# radio_hub_module.net
KiCad netlist of a schematic drawn in EAGLE
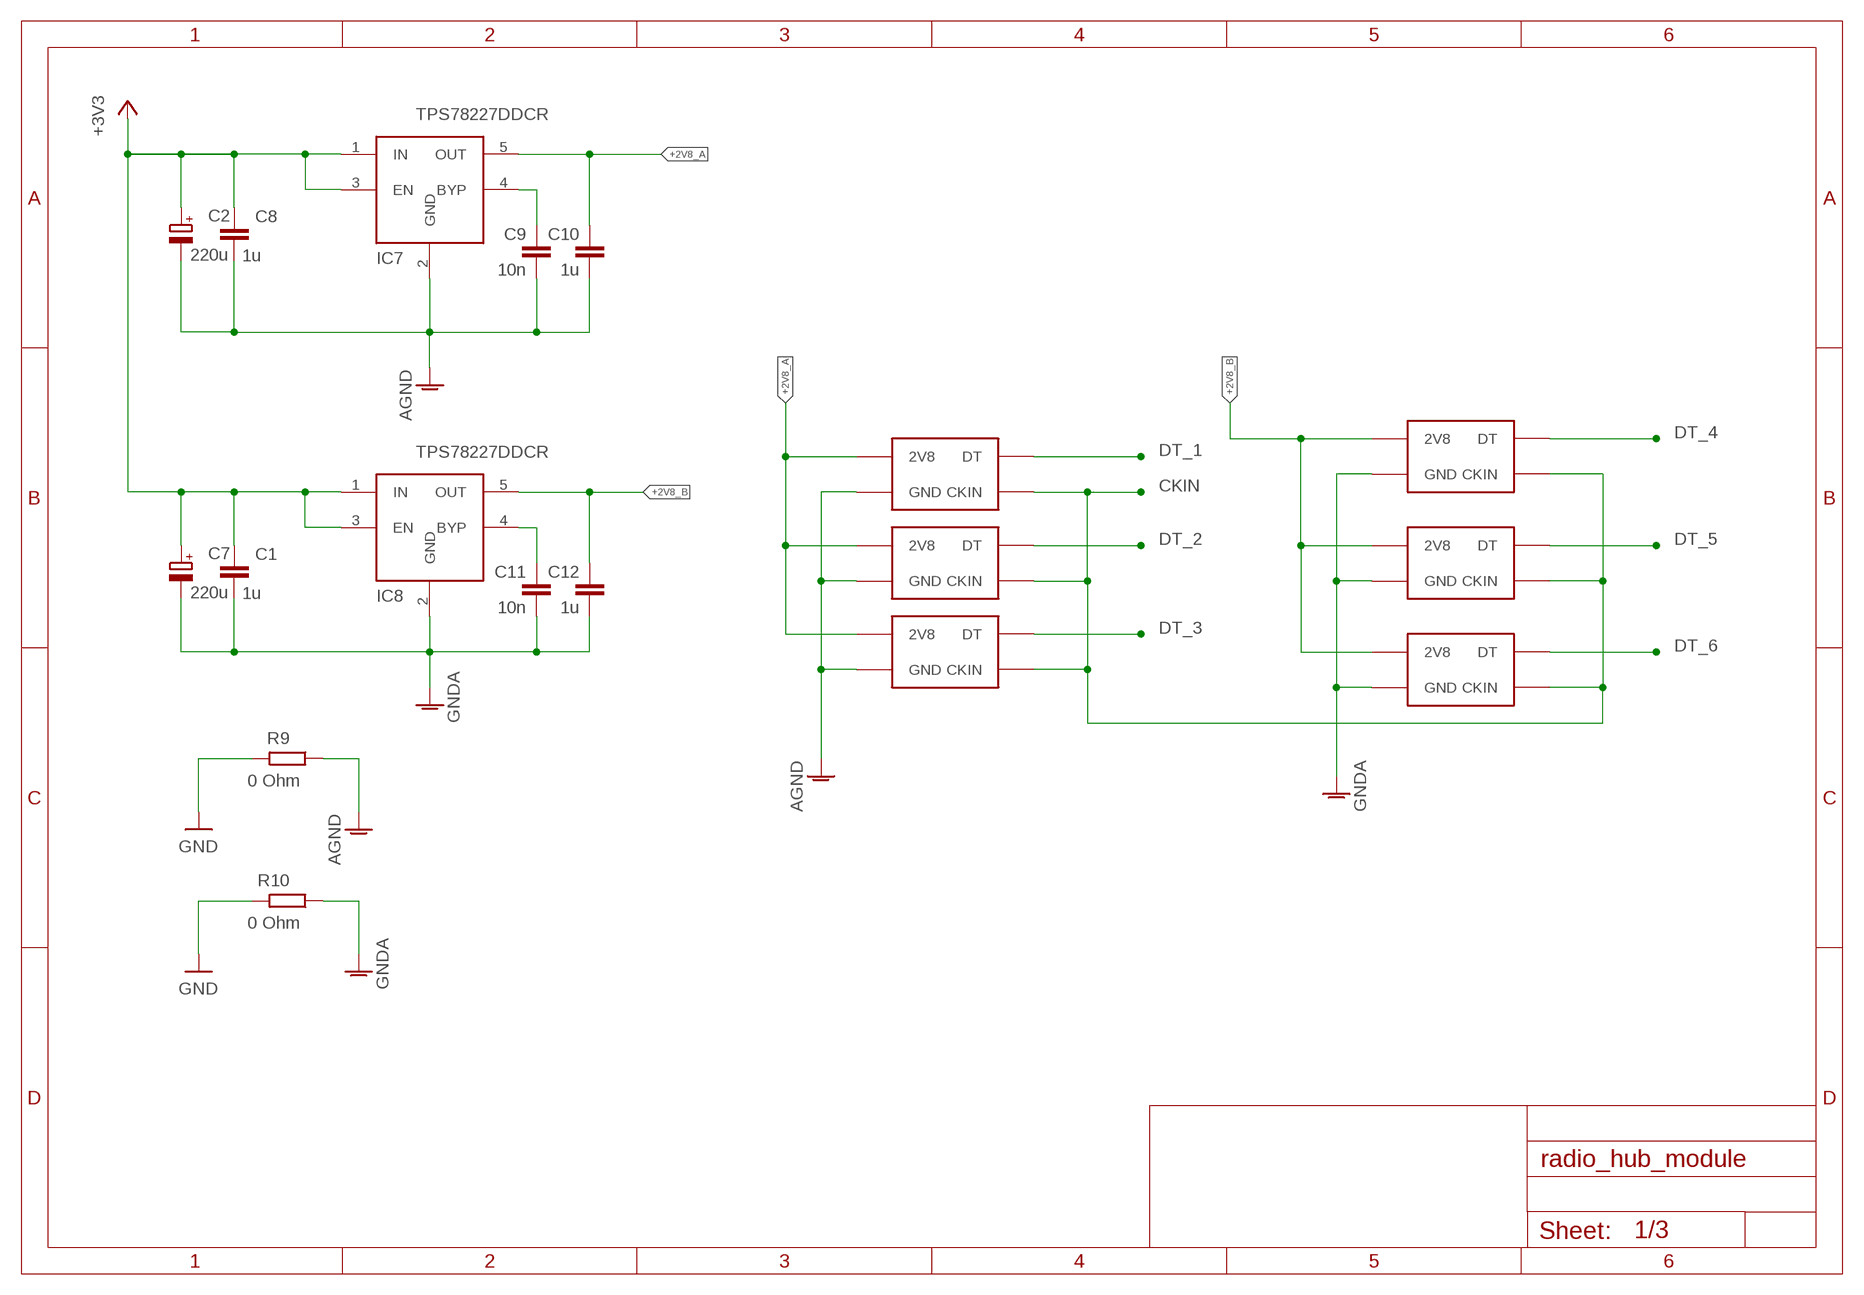
[diagram p0: schematic, sheet 1]
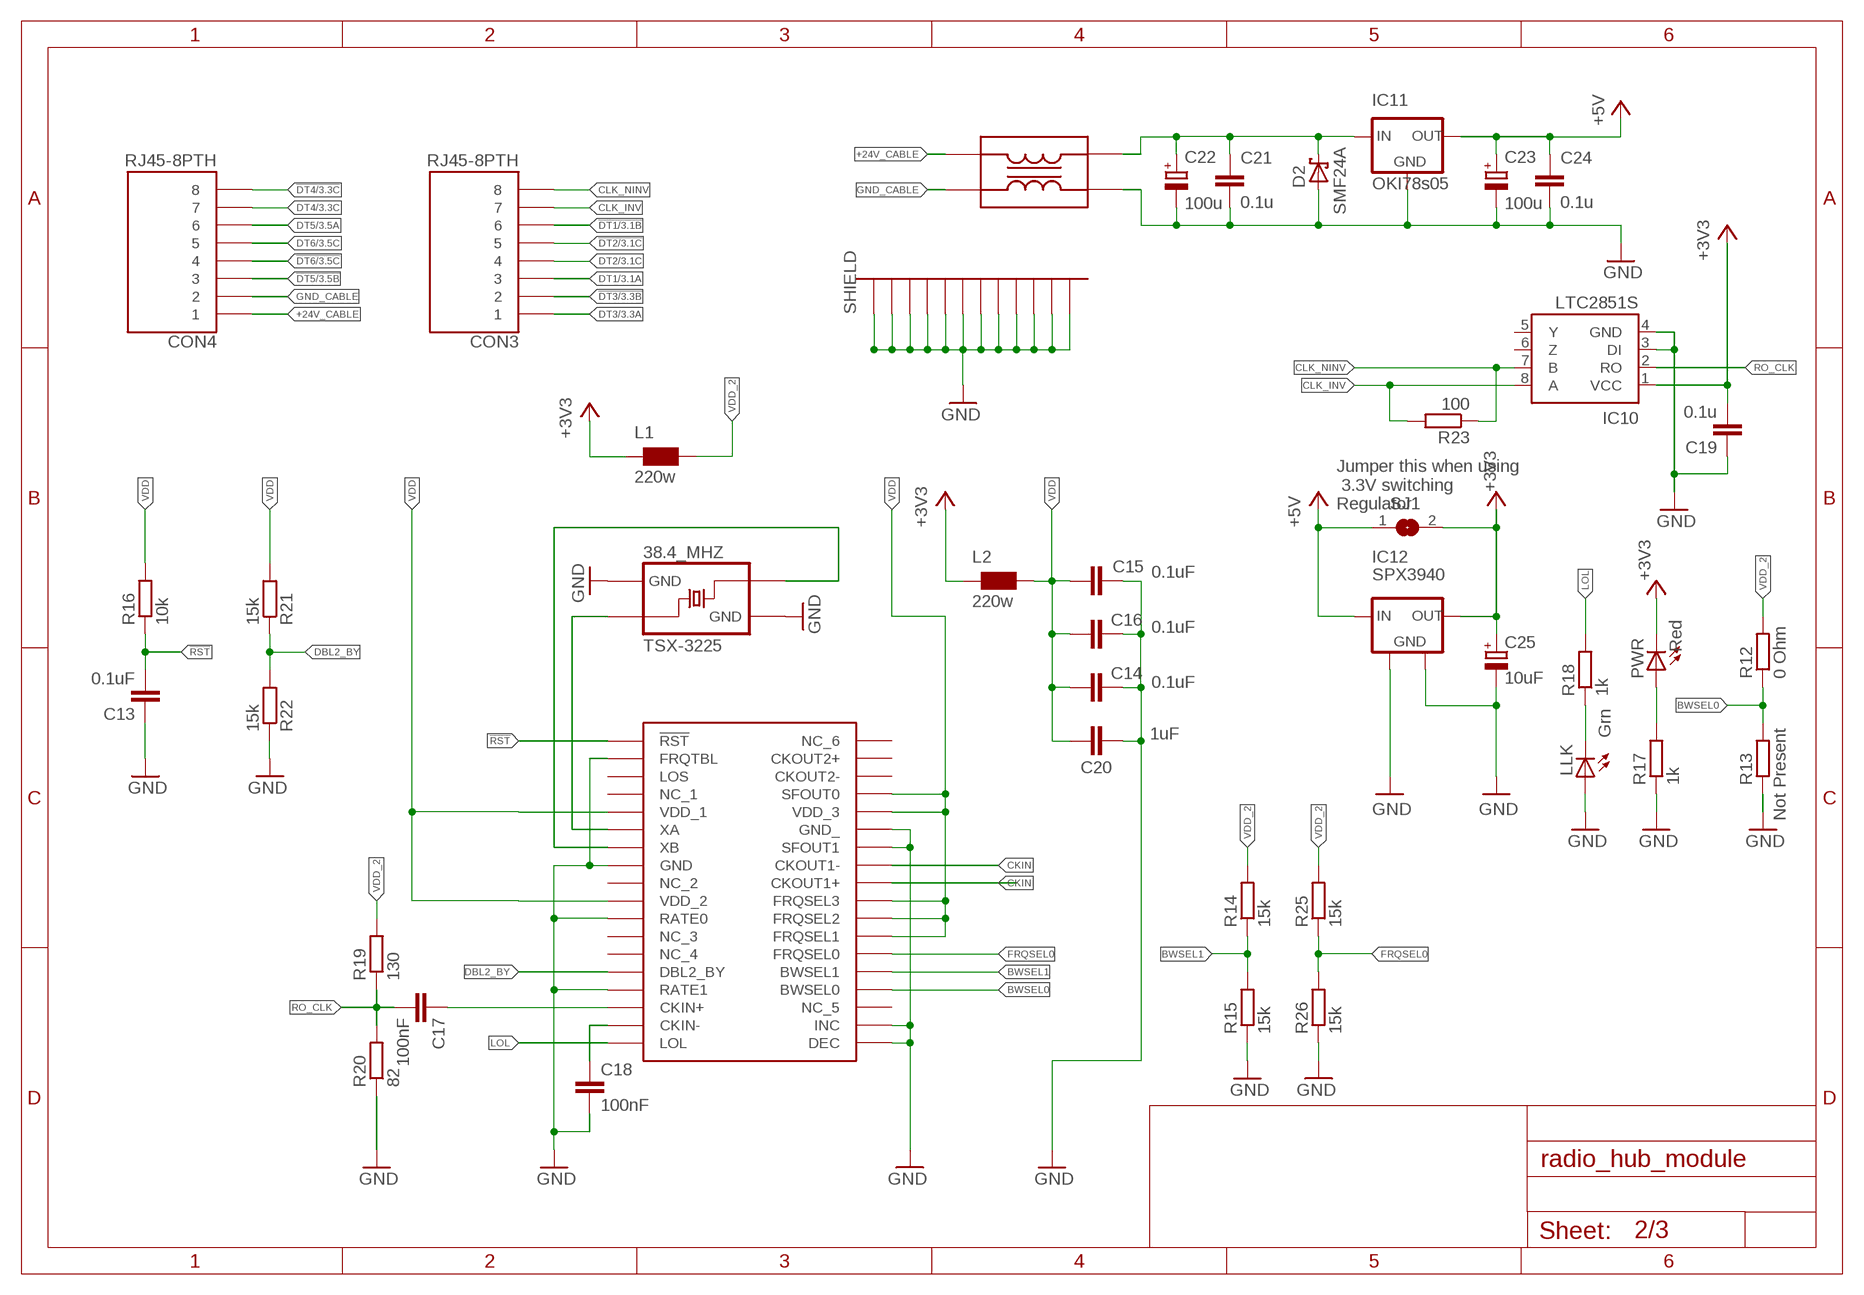
[diagram p1: schematic, sheet 2]
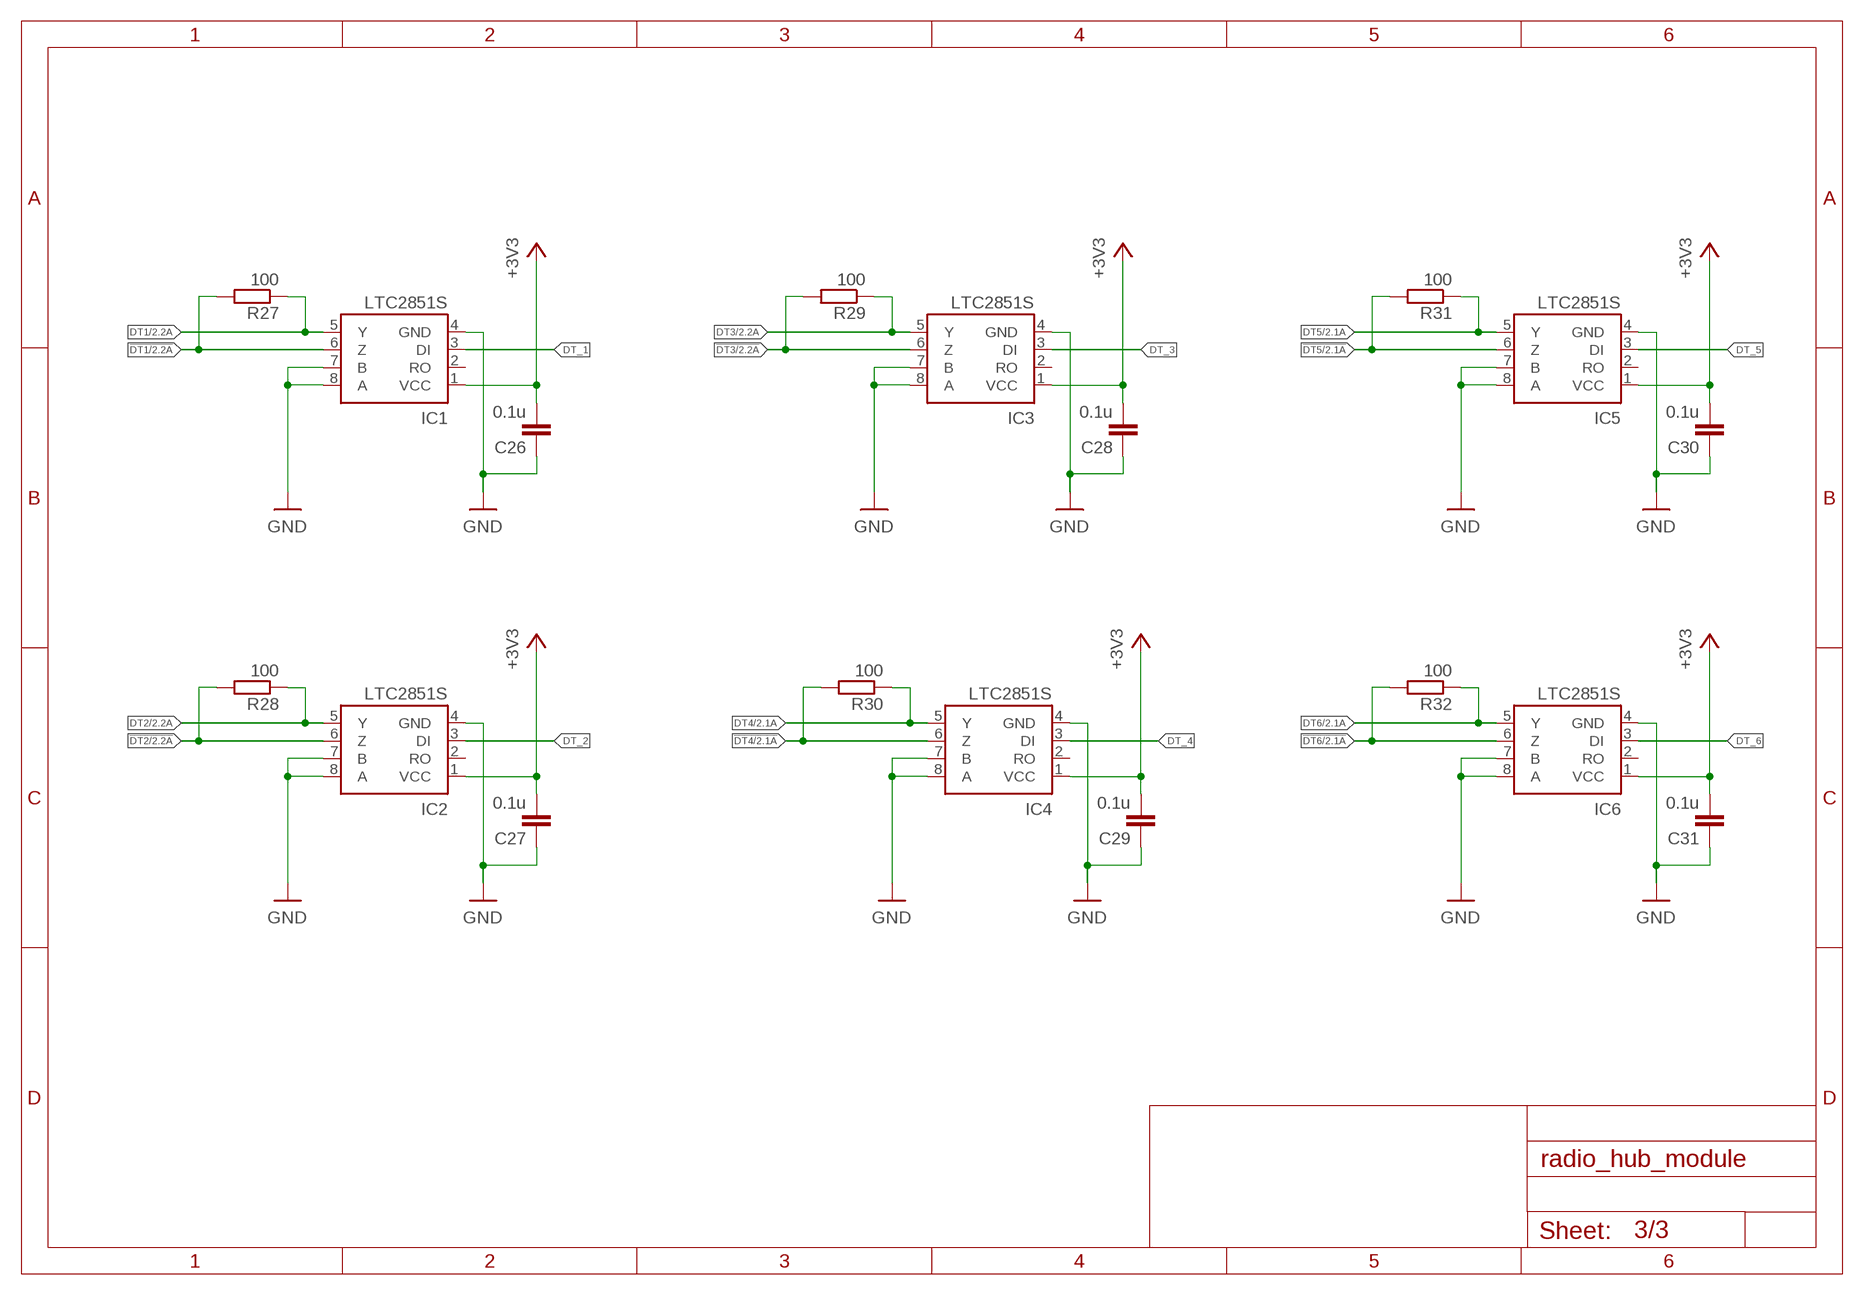
[diagram p2: schematic, sheet 3]

(export (version "E")
  (design (tool "Eeschema 10.0.6"))
  (components
    (comp (ref "C1")
      (value "1u")
      (footprint "eagle-import:C0603")
      (libsource (lib "eagle-import") (part "C-EUC0603"))
    )
    (comp (ref "C2")
      (value "220u")
      (footprint "eagle-import:C1210")
      (libsource (lib "eagle-import") (part "CPOL-EU1210"))
    )
    (comp (ref "C7")
      (value "220u")
      (footprint "eagle-import:C1210")
      (libsource (lib "eagle-import") (part "CPOL-EU1210"))
    )
    (comp (ref "C8")
      (value "1u")
      (footprint "eagle-import:C0603")
      (libsource (lib "eagle-import") (part "C-EUC0603"))
    )
    (comp (ref "C9")
      (value "10n")
      (footprint "eagle-import:C0603")
      (libsource (lib "eagle-import") (part "C-EUC0603"))
    )
    (comp (ref "C10")
      (value "1u")
      (footprint "eagle-import:C0603")
      (libsource (lib "eagle-import") (part "C-EUC0603"))
    )
    (comp (ref "C11")
      (value "10n")
      (footprint "eagle-import:C0603")
      (libsource (lib "eagle-import") (part "C-EUC0603"))
    )
    (comp (ref "C12")
      (value "1u")
      (footprint "eagle-import:C0603")
      (libsource (lib "eagle-import") (part "C-EUC0603"))
    )
    (comp (ref "IC7")
      (value "TPS78227DDCR")
      (footprint "eagle-import:SOT23-5")
      (libsource (lib "eagle-import") (part "NCP700BSN"))
    )
    (comp (ref "IC8")
      (value "TPS78227DDCR")
      (footprint "eagle-import:SOT23-5")
      (libsource (lib "eagle-import") (part "NCP700BSN"))
    )
    (comp (ref "MOD_1")
      (value "GPS_RADIO_MODULE")
      (footprint "eagle-import:GPS_RADIO_MODULE")
      (libsource (lib "eagle-import") (part "GPS_RADIO_MODULE"))
    )
    (comp (ref "MOD_2")
      (value "GPS_RADIO_MODULE")
      (footprint "eagle-import:GPS_RADIO_MODULE")
      (libsource (lib "eagle-import") (part "GPS_RADIO_MODULE"))
    )
    (comp (ref "MOD_3")
      (value "GPS_RADIO_MODULE")
      (footprint "eagle-import:GPS_RADIO_MODULE")
      (libsource (lib "eagle-import") (part "GPS_RADIO_MODULE"))
    )
    (comp (ref "MOD_4")
      (value "GPS_RADIO_MODULE")
      (footprint "eagle-import:GPS_RADIO_MODULE")
      (libsource (lib "eagle-import") (part "GPS_RADIO_MODULE"))
    )
    (comp (ref "MOD_5")
      (value "GPS_RADIO_MODULE")
      (footprint "eagle-import:GPS_RADIO_MODULE")
      (libsource (lib "eagle-import") (part "GPS_RADIO_MODULE"))
    )
    (comp (ref "MOD_6")
      (value "GPS_RADIO_MODULE")
      (footprint "eagle-import:GPS_RADIO_MODULE")
      (libsource (lib "eagle-import") (part "GPS_RADIO_MODULE"))
    )
    (comp (ref "R9")
      (value "0 Ohm")
      (footprint "eagle-import:R0805")
      (libsource (lib "eagle-import") (part "R-EU_R0805"))
    )
    (comp (ref "R10")
      (value "0 Ohm")
      (footprint "eagle-import:R0805")
      (libsource (lib "eagle-import") (part "R-EU_R0805"))
    )
    (comp (ref "C26")
      (value "0.1u")
      (footprint "eagle-import:C0805")
      (libsource (lib "eagle-import") (part "C-EUC0805"))
    )
    (comp (ref "C27")
      (value "0.1u")
      (footprint "eagle-import:C0805")
      (libsource (lib "eagle-import") (part "C-EUC0805"))
    )
    (comp (ref "C28")
      (value "0.1u")
      (footprint "eagle-import:C0805")
      (libsource (lib "eagle-import") (part "C-EUC0805"))
    )
    (comp (ref "C29")
      (value "0.1u")
      (footprint "eagle-import:C0805")
      (libsource (lib "eagle-import") (part "C-EUC0805"))
    )
    (comp (ref "C30")
      (value "0.1u")
      (footprint "eagle-import:C0805")
      (libsource (lib "eagle-import") (part "C-EUC0805"))
    )
    (comp (ref "C31")
      (value "0.1u")
      (footprint "eagle-import:C0805")
      (libsource (lib "eagle-import") (part "C-EUC0805"))
    )
    (comp (ref "IC1")
      (value "LTC2851S")
      (footprint "eagle-import:SOIC8")
      (libsource (lib "eagle-import") (part "LTC2851S"))
    )
    (comp (ref "IC2")
      (value "LTC2851S")
      (footprint "eagle-import:SOIC8")
      (libsource (lib "eagle-import") (part "LTC2851S"))
    )
    (comp (ref "IC3")
      (value "LTC2851S")
      (footprint "eagle-import:SOIC8")
      (libsource (lib "eagle-import") (part "LTC2851S"))
    )
    (comp (ref "IC4")
      (value "LTC2851S")
      (footprint "eagle-import:SOIC8")
      (libsource (lib "eagle-import") (part "LTC2851S"))
    )
    (comp (ref "IC5")
      (value "LTC2851S")
      (footprint "eagle-import:SOIC8")
      (libsource (lib "eagle-import") (part "LTC2851S"))
    )
    (comp (ref "IC6")
      (value "LTC2851S")
      (footprint "eagle-import:SOIC8")
      (libsource (lib "eagle-import") (part "LTC2851S"))
    )
    (comp (ref "R27")
      (value "100")
      (footprint "eagle-import:R0603")
      (libsource (lib "eagle-import") (part "R-EU_R0603"))
    )
    (comp (ref "R28")
      (value "100")
      (footprint "eagle-import:R0603")
      (libsource (lib "eagle-import") (part "R-EU_R0603"))
    )
    (comp (ref "R29")
      (value "100")
      (footprint "eagle-import:R0603")
      (libsource (lib "eagle-import") (part "R-EU_R0603"))
    )
    (comp (ref "R30")
      (value "100")
      (footprint "eagle-import:R0603")
      (libsource (lib "eagle-import") (part "R-EU_R0603"))
    )
    (comp (ref "R31")
      (value "100")
      (footprint "eagle-import:R0603")
      (libsource (lib "eagle-import") (part "R-EU_R0603"))
    )
    (comp (ref "R32")
      (value "100")
      (footprint "eagle-import:R0603")
      (libsource (lib "eagle-import") (part "R-EU_R0603"))
    )
    (comp (ref "38.4_MHZ")
      (value "TSX-3225")
      (footprint "eagle-import:TSX-3225")
      (libsource (lib "eagle-import") (part "TSX-3225"))
    )
    (comp (ref "C13")
      (value "0.1uF")
      (footprint "eagle-import:C0402")
      (libsource (lib "eagle-import") (part "C-EUC0402"))
    )
    (comp (ref "C14")
      (value "0.1uF")
      (footprint "eagle-import:C0402")
      (libsource (lib "eagle-import") (part "C-EUC0402"))
    )
    (comp (ref "C15")
      (value "0.1uF")
      (footprint "eagle-import:C0402")
      (libsource (lib "eagle-import") (part "C-EUC0402"))
    )
    (comp (ref "C16")
      (value "0.1uF")
      (footprint "eagle-import:C0402")
      (libsource (lib "eagle-import") (part "C-EUC0402"))
    )
    (comp (ref "C17")
      (value "100nF")
      (footprint "eagle-import:C0402")
      (libsource (lib "eagle-import") (part "C-EUC0402"))
    )
    (comp (ref "C18")
      (value "100nF")
      (footprint "eagle-import:C0402")
      (libsource (lib "eagle-import") (part "C-EUC0402"))
    )
    (comp (ref "C19")
      (value "0.1u")
      (footprint "eagle-import:C0805")
      (libsource (lib "eagle-import") (part "C-EUC0805"))
    )
    (comp (ref "C20")
      (value "1uF")
      (footprint "eagle-import:C0402")
      (libsource (lib "eagle-import") (part "C-EUC0402"))
    )
    (comp (ref "C21")
      (value "0.1u")
      (footprint "eagle-import:C0805")
      (libsource (lib "eagle-import") (part "C-EUC0805"))
    )
    (comp (ref "C22")
      (value "100u")
      (footprint "eagle-import:E5-10,5")
      (libsource (lib "eagle-import") (part "CPOL-EUE5-10.5"))
    )
    (comp (ref "C23")
      (value "100u")
      (footprint "eagle-import:E5-10,5")
      (libsource (lib "eagle-import") (part "CPOL-EUE5-10.5"))
    )
    (comp (ref "C24")
      (value "0.1u")
      (footprint "eagle-import:C0805")
      (libsource (lib "eagle-import") (part "C-EUC0805"))
    )
    (comp (ref "C25")
      (value "10uF")
      (footprint "eagle-import:E2-5")
      (libsource (lib "eagle-import") (part "CPOL-EUE2-5"))
    )
    (comp (ref "CON3")
      (value "RJ45-8PTH")
      (footprint "eagle-import:RJ45-8")
      (libsource (lib "eagle-import") (part "RJ45-8PTH"))
    )
    (comp (ref "CON4")
      (value "RJ45-8PTH")
      (footprint "eagle-import:RJ45-8")
      (libsource (lib "eagle-import") (part "RJ45-8PTH"))
    )
    (comp (ref "D2")
      (value "SMF24A")
      (footprint "eagle-import:SOD123")
      (libsource (lib "eagle-import") (part "SMF24A"))
    )
    (comp (ref "IC9")
      (value "SI5317")
      (footprint "eagle-import:QFN-36")
      (libsource (lib "eagle-import") (part "SI5317"))
    )
    (comp (ref "IC10")
      (value "LTC2851S")
      (footprint "eagle-import:SOIC8")
      (libsource (lib "eagle-import") (part "LTC2851S"))
    )
    (comp (ref "IC11")
      (value "OKI78s05")
      (footprint "eagle-import:TO220-IGO")
      (libsource (lib "eagle-import") (part "V_REG_OKI-78SRSINK"))
    )
    (comp (ref "IC12")
      (value "SPX3940")
      (footprint "eagle-import:SOT223")
      (libsource (lib "eagle-import") (part "SPX3940"))
    )
    (comp (ref "L1")
      (value "220w")
      (footprint "eagle-import:0805")
      (libsource (lib "eagle-import") (part "WE-CBF_0805"))
    )
    (comp (ref "L2")
      (value "220w")
      (footprint "eagle-import:0805")
      (libsource (lib "eagle-import") (part "WE-CBF_0805"))
    )
    (comp (ref "L3")
      (value "ACM3225-601-2P-T001")
      (footprint "eagle-import:ACM3225-601-2P-T001")
      (libsource (lib "eagle-import") (part "ACM3225-601-2P-T001"))
    )
    (comp (ref "LLK")
      (value "Grn")
      (footprint "eagle-import:CHIPLED_0805")
      (libsource (lib "eagle-import") (part "LEDCHIPLED_0805"))
    )
    (comp (ref "PWR")
      (value "Red")
      (footprint "eagle-import:CHIPLED_0805")
      (libsource (lib "eagle-import") (part "LEDCHIPLED_0805"))
    )
    (comp (ref "R12")
      (value "0 Ohm")
      (footprint "eagle-import:R0603")
      (libsource (lib "eagle-import") (part "resistor_R-EU_R0603"))
    )
    (comp (ref "R13")
      (value "Not Present")
      (footprint "eagle-import:R0603")
      (libsource (lib "eagle-import") (part "resistor_R-EU_R0603"))
    )
    (comp (ref "R14")
      (value "15k")
      (footprint "eagle-import:R0603")
      (libsource (lib "eagle-import") (part "resistor_R-EU_R0603"))
    )
    (comp (ref "R15")
      (value "15k")
      (footprint "eagle-import:R0603")
      (libsource (lib "eagle-import") (part "resistor_R-EU_R0603"))
    )
    (comp (ref "R16")
      (value "10k")
      (footprint "eagle-import:R0402")
      (libsource (lib "eagle-import") (part "R-EU_R0402"))
    )
    (comp (ref "R17")
      (value "1k")
      (footprint "eagle-import:R0603")
      (libsource (lib "eagle-import") (part "R-EU_R0603"))
    )
    (comp (ref "R18")
      (value "1k")
      (footprint "eagle-import:R0603")
      (libsource (lib "eagle-import") (part "R-EU_R0603"))
    )
    (comp (ref "R19")
      (value "130")
      (footprint "eagle-import:R0603")
      (libsource (lib "eagle-import") (part "resistor_R-EU_R0603"))
    )
    (comp (ref "R20")
      (value "82")
      (footprint "eagle-import:R0603")
      (libsource (lib "eagle-import") (part "resistor_R-EU_R0603"))
    )
    (comp (ref "R21")
      (value "15k")
      (footprint "eagle-import:R0603")
      (libsource (lib "eagle-import") (part "resistor_R-EU_R0603"))
    )
    (comp (ref "R22")
      (value "15k")
      (footprint "eagle-import:R0603")
      (libsource (lib "eagle-import") (part "resistor_R-EU_R0603"))
    )
    (comp (ref "R23")
      (value "100")
      (footprint "eagle-import:R0603")
      (libsource (lib "eagle-import") (part "R-EU_R0603"))
    )
    (comp (ref "R25")
      (value "15k")
      (footprint "eagle-import:R0603")
      (libsource (lib "eagle-import") (part "resistor_R-EU_R0603"))
    )
    (comp (ref "R26")
      (value "15k")
      (footprint "eagle-import:R0603")
      (libsource (lib "eagle-import") (part "resistor_R-EU_R0603"))
    )
    (comp (ref "SH1")
      (value "BMIS-202")
      (footprint "eagle-import:BMIS-202")
      (libsource (lib "eagle-import") (part "BMIS-202"))
    )
    (comp (ref "SJ1") (value "SJ") (footprint "eagle-import:SJ") (libsource (lib "eagle-import") (part "SJ")))
  )
  (nets
    (net (code "1") (name "+2V8_A") (class "Default")
      (node (ref "C10") (pin "1") (pinfunction "1_1") (pintype "passive"))
      (node (ref "IC7") (pin "5") (pinfunction "OUT_5") (pintype "power_in"))
      (node (ref "MOD_1") (pin "2V8@11") (pinfunction "2V8_2V8@11") (pintype "power_in"))
      (node (ref "MOD_1") (pin "2V8@15") (pinfunction "2V8_2V8@15") (pintype "power_in"))
      (node (ref "MOD_1") (pin "2V8@16") (pinfunction "2V8_2V8@16") (pintype "power_in"))
      (node (ref "MOD_2") (pin "2V8@11") (pinfunction "2V8_2V8@11") (pintype "power_in"))
      (node (ref "MOD_2") (pin "2V8@15") (pinfunction "2V8_2V8@15") (pintype "power_in"))
      (node (ref "MOD_2") (pin "2V8@16") (pinfunction "2V8_2V8@16") (pintype "power_in"))
      (node (ref "MOD_3") (pin "2V8@11") (pinfunction "2V8_2V8@11") (pintype "power_in"))
      (node (ref "MOD_3") (pin "2V8@15") (pinfunction "2V8_2V8@15") (pintype "power_in"))
      (node (ref "MOD_3") (pin "2V8@16") (pinfunction "2V8_2V8@16") (pintype "power_in"))
    )
    (net (code "2") (name "+2V8_B") (class "Default")
      (node (ref "C12") (pin "1") (pinfunction "1_1") (pintype "passive"))
      (node (ref "IC8") (pin "5") (pinfunction "OUT_5") (pintype "power_in"))
      (node (ref "MOD_4") (pin "2V8@11") (pinfunction "2V8_2V8@11") (pintype "power_in"))
      (node (ref "MOD_4") (pin "2V8@15") (pinfunction "2V8_2V8@15") (pintype "power_in"))
      (node (ref "MOD_4") (pin "2V8@16") (pinfunction "2V8_2V8@16") (pintype "power_in"))
      (node (ref "MOD_5") (pin "2V8@11") (pinfunction "2V8_2V8@11") (pintype "power_in"))
      (node (ref "MOD_5") (pin "2V8@15") (pinfunction "2V8_2V8@15") (pintype "power_in"))
      (node (ref "MOD_5") (pin "2V8@16") (pinfunction "2V8_2V8@16") (pintype "power_in"))
      (node (ref "MOD_6") (pin "2V8@11") (pinfunction "2V8_2V8@11") (pintype "power_in"))
      (node (ref "MOD_6") (pin "2V8@15") (pinfunction "2V8_2V8@15") (pintype "power_in"))
      (node (ref "MOD_6") (pin "2V8@16") (pinfunction "2V8_2V8@16") (pintype "power_in"))
    )
    (net (code "3") (name "+3V3") (class "Default")
      (node (ref "C1") (pin "1") (pinfunction "1_1") (pintype "passive"))
      (node (ref "C19") (pin "2") (pinfunction "2_2") (pintype "passive"))
      (node (ref "C2") (pin "1") (pinfunction "+_1") (pintype "passive"))
      (node (ref "C25") (pin "+") (pinfunction "+_+") (pintype "passive"))
      (node (ref "C26") (pin "2") (pinfunction "2_2") (pintype "passive"))
      (node (ref "C27") (pin "2") (pinfunction "2_2") (pintype "passive"))
      (node (ref "C28") (pin "2") (pinfunction "2_2") (pintype "passive"))
      (node (ref "C29") (pin "2") (pinfunction "2_2") (pintype "passive"))
      (node (ref "C30") (pin "2") (pinfunction "2_2") (pintype "passive"))
      (node (ref "C31") (pin "2") (pinfunction "2_2") (pintype "passive"))
      (node (ref "C7") (pin "1") (pinfunction "+_1") (pintype "passive"))
      (node (ref "C8") (pin "1") (pinfunction "1_1") (pintype "passive"))
      (node (ref "IC1") (pin "1") (pinfunction "VCC_1") (pintype "power_in"))
      (node (ref "IC10") (pin "1") (pinfunction "VCC_1") (pintype "power_in"))
      (node (ref "IC12") (pin "3") (pinfunction "OUT_3") (pintype "power_in"))
      (node (ref "IC2") (pin "1") (pinfunction "VCC_1") (pintype "power_in"))
      (node (ref "IC3") (pin "1") (pinfunction "VCC_1") (pintype "power_in"))
      (node (ref "IC4") (pin "1") (pinfunction "VCC_1") (pintype "power_in"))
      (node (ref "IC5") (pin "1") (pinfunction "VCC_1") (pintype "power_in"))
      (node (ref "IC6") (pin "1") (pinfunction "VCC_1") (pintype "power_in"))
      (node (ref "IC7") (pin "1") (pinfunction "IN_1") (pintype "power_in"))
      (node (ref "IC7") (pin "3") (pinfunction "EN_3") (pintype "input"))
      (node (ref "IC8") (pin "1") (pinfunction "IN_1") (pintype "power_in"))
      (node (ref "IC8") (pin "3") (pinfunction "EN_3") (pintype "input"))
      (node (ref "L1") (pin "1") (pinfunction "1_1") (pintype "passive"))
      (node (ref "L2") (pin "1") (pinfunction "1_1") (pintype "passive"))
      (node (ref "PWR") (pin "C") (pinfunction "C_C") (pintype "passive"))
      (node (ref "SJ1") (pin "2") (pinfunction "2_2") (pintype "passive"))
    )
    (net (code "4") (name "+5V") (class "Default")
      (node (ref "C23") (pin "+") (pinfunction "+_+") (pintype "passive"))
      (node (ref "C24") (pin "1") (pinfunction "1_1") (pintype "passive"))
      (node (ref "IC11") (pin "OUT") (pinfunction "OUT_OUT") (pintype "output"))
      (node (ref "IC12") (pin "1") (pinfunction "IN_1") (pintype "power_in"))
      (node (ref "SJ1") (pin "1") (pinfunction "1_1") (pintype "passive"))
    )
    (net (code "5") (name "+24V_CABLE") (class "Default")
      (node (ref "CON4") (pin "1") (pinfunction "1_1") (pintype "bidirectional"))
      (node (ref "L3") (pin "1") (pinfunction "1_1") (pintype "power_in"))
    )
    (net (code "6") (name "AGND") (class "Default")
      (node (ref "C10") (pin "2") (pinfunction "2_2") (pintype "passive"))
      (node (ref "C2") (pin "2") (pinfunction "-_2") (pintype "passive"))
      (node (ref "C8") (pin "2") (pinfunction "2_2") (pintype "passive"))
      (node (ref "C9") (pin "2") (pinfunction "2_2") (pintype "passive"))
      (node (ref "IC7") (pin "2") (pinfunction "GND_2") (pintype "power_in"))
      (node (ref "MOD_1") (pin "GND@1") (pinfunction "GND_GND@1") (pintype "power_in"))
      (node (ref "MOD_1") (pin "GND@10") (pinfunction "GND_GND@10") (pintype "power_in"))
      (node (ref "MOD_1") (pin "GND@14") (pinfunction "GND_GND@14") (pintype "power_in"))
      (node (ref "MOD_1") (pin "GND@2") (pinfunction "GND_GND@2") (pintype "power_in"))
      (node (ref "MOD_1") (pin "GND@3") (pinfunction "GND_GND@3") (pintype "power_in"))
      (node (ref "MOD_1") (pin "GND@4") (pinfunction "GND_GND@4") (pintype "power_in"))
      (node (ref "MOD_1") (pin "GND@5") (pinfunction "GND_GND@5") (pintype "power_in"))
      (node (ref "MOD_1") (pin "GND@6") (pinfunction "GND_GND@6") (pintype "power_in"))
      (node (ref "MOD_1") (pin "GND@7") (pinfunction "GND_GND@7") (pintype "power_in"))
      (node (ref "MOD_1") (pin "GND@8") (pinfunction "GND_GND@8") (pintype "power_in"))
      (node (ref "MOD_1") (pin "GND@9") (pinfunction "GND_GND@9") (pintype "power_in"))
      (node (ref "MOD_1") (pin "V1") (pinfunction "GND_V1") (pintype "power_in"))
      (node (ref "MOD_1") (pin "V10") (pinfunction "GND_V10") (pintype "power_in"))
      (node (ref "MOD_1") (pin "V11") (pinfunction "GND_V11") (pintype "power_in"))
      (node (ref "MOD_1") (pin "V12") (pinfunction "GND_V12") (pintype "power_in"))
      (node (ref "MOD_1") (pin "V13") (pinfunction "GND_V13") (pintype "power_in"))
      (node (ref "MOD_1") (pin "V14") (pinfunction "GND_V14") (pintype "power_in"))
      (node (ref "MOD_1") (pin "V15") (pinfunction "GND_V15") (pintype "power_in"))
      (node (ref "MOD_1") (pin "V16") (pinfunction "GND_V16") (pintype "power_in"))
      (node (ref "MOD_1") (pin "V17") (pinfunction "GND_V17") (pintype "power_in"))
      (node (ref "MOD_1") (pin "V18") (pinfunction "GND_V18") (pintype "power_in"))
      (node (ref "MOD_1") (pin "V19") (pinfunction "GND_V19") (pintype "power_in"))
      (node (ref "MOD_1") (pin "V2") (pinfunction "GND_V2") (pintype "power_in"))
      (node (ref "MOD_1") (pin "V20") (pinfunction "GND_V20") (pintype "power_in"))
      (node (ref "MOD_1") (pin "V21") (pinfunction "GND_V21") (pintype "power_in"))
      (node (ref "MOD_1") (pin "V22") (pinfunction "GND_V22") (pintype "power_in"))
      (node (ref "MOD_1") (pin "V23") (pinfunction "GND_V23") (pintype "power_in"))
      (node (ref "MOD_1") (pin "V24") (pinfunction "GND_V24") (pintype "power_in"))
      (node (ref "MOD_1") (pin "V25") (pinfunction "GND_V25") (pintype "power_in"))
      (node (ref "MOD_1") (pin "V26") (pinfunction "GND_V26") (pintype "power_in"))
      (node (ref "MOD_1") (pin "V27") (pinfunction "GND_V27") (pintype "power_in"))
      (node (ref "MOD_1") (pin "V28") (pinfunction "GND_V28") (pintype "power_in"))
      (node (ref "MOD_1") (pin "V29") (pinfunction "GND_V29") (pintype "power_in"))
      (node (ref "MOD_1") (pin "V3") (pinfunction "GND_V3") (pintype "power_in"))
      (node (ref "MOD_1") (pin "V30") (pinfunction "GND_V30") (pintype "power_in"))
      (node (ref "MOD_1") (pin "V4") (pinfunction "GND_V4") (pintype "power_in"))
      (node (ref "MOD_1") (pin "V5") (pinfunction "GND_V5") (pintype "power_in"))
      (node (ref "MOD_1") (pin "V6") (pinfunction "GND_V6") (pintype "power_in"))
      (node (ref "MOD_1") (pin "V7") (pinfunction "GND_V7") (pintype "power_in"))
      (node (ref "MOD_1") (pin "V8") (pinfunction "GND_V8") (pintype "power_in"))
      (node (ref "MOD_1") (pin "V9") (pinfunction "GND_V9") (pintype "power_in"))
      (node (ref "MOD_2") (pin "GND@1") (pinfunction "GND_GND@1") (pintype "power_in"))
      (node (ref "MOD_2") (pin "GND@10") (pinfunction "GND_GND@10") (pintype "power_in"))
      (node (ref "MOD_2") (pin "GND@14") (pinfunction "GND_GND@14") (pintype "power_in"))
      (node (ref "MOD_2") (pin "GND@2") (pinfunction "GND_GND@2") (pintype "power_in"))
      (node (ref "MOD_2") (pin "GND@3") (pinfunction "GND_GND@3") (pintype "power_in"))
      (node (ref "MOD_2") (pin "GND@4") (pinfunction "GND_GND@4") (pintype "power_in"))
      (node (ref "MOD_2") (pin "GND@5") (pinfunction "GND_GND@5") (pintype "power_in"))
      (node (ref "MOD_2") (pin "GND@6") (pinfunction "GND_GND@6") (pintype "power_in"))
      (node (ref "MOD_2") (pin "GND@7") (pinfunction "GND_GND@7") (pintype "power_in"))
      (node (ref "MOD_2") (pin "GND@8") (pinfunction "GND_GND@8") (pintype "power_in"))
      (node (ref "MOD_2") (pin "GND@9") (pinfunction "GND_GND@9") (pintype "power_in"))
      (node (ref "MOD_2") (pin "V1") (pinfunction "GND_V1") (pintype "power_in"))
      (node (ref "MOD_2") (pin "V10") (pinfunction "GND_V10") (pintype "power_in"))
      (node (ref "MOD_2") (pin "V11") (pinfunction "GND_V11") (pintype "power_in"))
      (node (ref "MOD_2") (pin "V12") (pinfunction "GND_V12") (pintype "power_in"))
      (node (ref "MOD_2") (pin "V13") (pinfunction "GND_V13") (pintype "power_in"))
      (node (ref "MOD_2") (pin "V14") (pinfunction "GND_V14") (pintype "power_in"))
      (node (ref "MOD_2") (pin "V15") (pinfunction "GND_V15") (pintype "power_in"))
      (node (ref "MOD_2") (pin "V16") (pinfunction "GND_V16") (pintype "power_in"))
      (node (ref "MOD_2") (pin "V17") (pinfunction "GND_V17") (pintype "power_in"))
      (node (ref "MOD_2") (pin "V18") (pinfunction "GND_V18") (pintype "power_in"))
      (node (ref "MOD_2") (pin "V19") (pinfunction "GND_V19") (pintype "power_in"))
      (node (ref "MOD_2") (pin "V2") (pinfunction "GND_V2") (pintype "power_in"))
      (node (ref "MOD_2") (pin "V20") (pinfunction "GND_V20") (pintype "power_in"))
      (node (ref "MOD_2") (pin "V21") (pinfunction "GND_V21") (pintype "power_in"))
      (node (ref "MOD_2") (pin "V22") (pinfunction "GND_V22") (pintype "power_in"))
      (node (ref "MOD_2") (pin "V23") (pinfunction "GND_V23") (pintype "power_in"))
      (node (ref "MOD_2") (pin "V24") (pinfunction "GND_V24") (pintype "power_in"))
      (node (ref "MOD_2") (pin "V25") (pinfunction "GND_V25") (pintype "power_in"))
      (node (ref "MOD_2") (pin "V26") (pinfunction "GND_V26") (pintype "power_in"))
      (node (ref "MOD_2") (pin "V27") (pinfunction "GND_V27") (pintype "power_in"))
      (node (ref "MOD_2") (pin "V28") (pinfunction "GND_V28") (pintype "power_in"))
      (node (ref "MOD_2") (pin "V29") (pinfunction "GND_V29") (pintype "power_in"))
      (node (ref "MOD_2") (pin "V3") (pinfunction "GND_V3") (pintype "power_in"))
      (node (ref "MOD_2") (pin "V30") (pinfunction "GND_V30") (pintype "power_in"))
      (node (ref "MOD_2") (pin "V4") (pinfunction "GND_V4") (pintype "power_in"))
      (node (ref "MOD_2") (pin "V5") (pinfunction "GND_V5") (pintype "power_in"))
      (node (ref "MOD_2") (pin "V6") (pinfunction "GND_V6") (pintype "power_in"))
      (node (ref "MOD_2") (pin "V7") (pinfunction "GND_V7") (pintype "power_in"))
      (node (ref "MOD_2") (pin "V8") (pinfunction "GND_V8") (pintype "power_in"))
      (node (ref "MOD_2") (pin "V9") (pinfunction "GND_V9") (pintype "power_in"))
      (node (ref "MOD_3") (pin "GND@1") (pinfunction "GND_GND@1") (pintype "power_in"))
      (node (ref "MOD_3") (pin "GND@10") (pinfunction "GND_GND@10") (pintype "power_in"))
      (node (ref "MOD_3") (pin "GND@14") (pinfunction "GND_GND@14") (pintype "power_in"))
      (node (ref "MOD_3") (pin "GND@2") (pinfunction "GND_GND@2") (pintype "power_in"))
      (node (ref "MOD_3") (pin "GND@3") (pinfunction "GND_GND@3") (pintype "power_in"))
      (node (ref "MOD_3") (pin "GND@4") (pinfunction "GND_GND@4") (pintype "power_in"))
      (node (ref "MOD_3") (pin "GND@5") (pinfunction "GND_GND@5") (pintype "power_in"))
      (node (ref "MOD_3") (pin "GND@6") (pinfunction "GND_GND@6") (pintype "power_in"))
      (node (ref "MOD_3") (pin "GND@7") (pinfunction "GND_GND@7") (pintype "power_in"))
      (node (ref "MOD_3") (pin "GND@8") (pinfunction "GND_GND@8") (pintype "power_in"))
      (node (ref "MOD_3") (pin "GND@9") (pinfunction "GND_GND@9") (pintype "power_in"))
      (node (ref "MOD_3") (pin "V1") (pinfunction "GND_V1") (pintype "power_in"))
      (node (ref "MOD_3") (pin "V10") (pinfunction "GND_V10") (pintype "power_in"))
      (node (ref "MOD_3") (pin "V11") (pinfunction "GND_V11") (pintype "power_in"))
      (node (ref "MOD_3") (pin "V12") (pinfunction "GND_V12") (pintype "power_in"))
      (node (ref "MOD_3") (pin "V13") (pinfunction "GND_V13") (pintype "power_in"))
      (node (ref "MOD_3") (pin "V14") (pinfunction "GND_V14") (pintype "power_in"))
      (node (ref "MOD_3") (pin "V15") (pinfunction "GND_V15") (pintype "power_in"))
      (node (ref "MOD_3") (pin "V16") (pinfunction "GND_V16") (pintype "power_in"))
      (node (ref "MOD_3") (pin "V17") (pinfunction "GND_V17") (pintype "power_in"))
      (node (ref "MOD_3") (pin "V18") (pinfunction "GND_V18") (pintype "power_in"))
      (node (ref "MOD_3") (pin "V19") (pinfunction "GND_V19") (pintype "power_in"))
      (node (ref "MOD_3") (pin "V2") (pinfunction "GND_V2") (pintype "power_in"))
      (node (ref "MOD_3") (pin "V20") (pinfunction "GND_V20") (pintype "power_in"))
      (node (ref "MOD_3") (pin "V21") (pinfunction "GND_V21") (pintype "power_in"))
      (node (ref "MOD_3") (pin "V22") (pinfunction "GND_V22") (pintype "power_in"))
      (node (ref "MOD_3") (pin "V23") (pinfunction "GND_V23") (pintype "power_in"))
      (node (ref "MOD_3") (pin "V24") (pinfunction "GND_V24") (pintype "power_in"))
      (node (ref "MOD_3") (pin "V25") (pinfunction "GND_V25") (pintype "power_in"))
      (node (ref "MOD_3") (pin "V26") (pinfunction "GND_V26") (pintype "power_in"))
      (node (ref "MOD_3") (pin "V27") (pinfunction "GND_V27") (pintype "power_in"))
      (node (ref "MOD_3") (pin "V28") (pinfunction "GND_V28") (pintype "power_in"))
      (node (ref "MOD_3") (pin "V29") (pinfunction "GND_V29") (pintype "power_in"))
      (node (ref "MOD_3") (pin "V3") (pinfunction "GND_V3") (pintype "power_in"))
      (node (ref "MOD_3") (pin "V30") (pinfunction "GND_V30") (pintype "power_in"))
      (node (ref "MOD_3") (pin "V4") (pinfunction "GND_V4") (pintype "power_in"))
      (node (ref "MOD_3") (pin "V5") (pinfunction "GND_V5") (pintype "power_in"))
      (node (ref "MOD_3") (pin "V6") (pinfunction "GND_V6") (pintype "power_in"))
      (node (ref "MOD_3") (pin "V7") (pinfunction "GND_V7") (pintype "power_in"))
      (node (ref "MOD_3") (pin "V8") (pinfunction "GND_V8") (pintype "power_in"))
      (node (ref "MOD_3") (pin "V9") (pinfunction "GND_V9") (pintype "power_in"))
      (node (ref "R9") (pin "1") (pinfunction "1_1") (pintype "passive"))
    )
    (net (code "7") (name "BWSEL0") (class "Default")
      (node (ref "IC9") (pin "22") (pinfunction "BWSEL0_22") (pintype "bidirectional"))
      (node (ref "R12") (pin "1") (pinfunction "1_1") (pintype "passive"))
      (node (ref "R13") (pin "2") (pinfunction "2_2") (pintype "passive"))
    )
    (net (code "8") (name "BWSEL1") (class "Default")
      (node (ref "IC9") (pin "23") (pinfunction "BWSEL1_23") (pintype "bidirectional"))
      (node (ref "R14") (pin "1") (pinfunction "1_1") (pintype "passive"))
      (node (ref "R15") (pin "2") (pinfunction "2_2") (pintype "passive"))
    )
    (net (code "9") (name "CKIN") (class "Default")
      (node (ref "IC9") (pin "28") (pinfunction "CKOUT1+_28") (pintype "bidirectional"))
      (node (ref "IC9") (pin "29") (pinfunction "CKOUT1-_29") (pintype "bidirectional"))
      (node (ref "MOD_1") (pin "CKIN@13") (pinfunction "CKIN_CKIN@13") (pintype "input"))
      (node (ref "MOD_2") (pin "CKIN@13") (pinfunction "CKIN_CKIN@13") (pintype "input"))
      (node (ref "MOD_3") (pin "CKIN@13") (pinfunction "CKIN_CKIN@13") (pintype "input"))
      (node (ref "MOD_4") (pin "CKIN@13") (pinfunction "CKIN_CKIN@13") (pintype "input"))
      (node (ref "MOD_5") (pin "CKIN@13") (pinfunction "CKIN_CKIN@13") (pintype "input"))
      (node (ref "MOD_6") (pin "CKIN@13") (pinfunction "CKIN_CKIN@13") (pintype "input"))
    )
    (net (code "10") (name "CLK_INV") (class "Default")
      (node (ref "CON3") (pin "7") (pinfunction "7_7") (pintype "bidirectional"))
      (node (ref "IC10") (pin "8") (pinfunction "A_8") (pintype "input"))
      (node (ref "R23") (pin "2") (pinfunction "2_2") (pintype "passive"))
    )
    (net (code "11") (name "CLK_NINV") (class "Default")
      (node (ref "CON3") (pin "8") (pinfunction "8_8") (pintype "bidirectional"))
      (node (ref "IC10") (pin "7") (pinfunction "B_7") (pintype "input"))
      (node (ref "R23") (pin "1") (pinfunction "1_1") (pintype "passive"))
    )
    (net (code "12") (name "DBL2_BY") (class "Default")
      (node (ref "IC9") (pin "14") (pinfunction "DBL2_BY_14") (pintype "bidirectional"))
      (node (ref "R21") (pin "1") (pinfunction "1_1") (pintype "passive"))
      (node (ref "R22") (pin "2") (pinfunction "2_2") (pintype "passive"))
    )
    (net (code "13") (name "DT1") (class "Default")
      (node (ref "CON3") (pin "3") (pinfunction "3_3") (pintype "bidirectional"))
      (node (ref "IC1") (pin "5") (pinfunction "Y_5") (pintype "output"))
      (node (ref "R27") (pin "1") (pinfunction "1_1") (pintype "passive"))
    )
    (net (code "14") (name "DT2") (class "Default")
      (node (ref "CON3") (pin "4") (pinfunction "4_4") (pintype "bidirectional"))
      (node (ref "IC2") (pin "5") (pinfunction "Y_5") (pintype "output"))
      (node (ref "R28") (pin "1") (pinfunction "1_1") (pintype "passive"))
    )
    (net (code "15") (name "DT3") (class "Default")
      (node (ref "CON3") (pin "1") (pinfunction "1_1") (pintype "bidirectional"))
      (node (ref "IC3") (pin "5") (pinfunction "Y_5") (pintype "output"))
      (node (ref "R29") (pin "1") (pinfunction "1_1") (pintype "passive"))
    )
    (net (code "16") (name "DT4") (class "Default")
      (node (ref "CON4") (pin "7") (pinfunction "7_7") (pintype "bidirectional"))
      (node (ref "IC4") (pin "5") (pinfunction "Y_5") (pintype "output"))
      (node (ref "R30") (pin "1") (pinfunction "1_1") (pintype "passive"))
    )
    (net (code "17") (name "DT5") (class "Default")
      (node (ref "CON4") (pin "6") (pinfunction "6_6") (pintype "bidirectional"))
      (node (ref "IC5") (pin "5") (pinfunction "Y_5") (pintype "output"))
      (node (ref "R31") (pin "1") (pinfunction "1_1") (pintype "passive"))
    )
    (net (code "18") (name "DT6") (class "Default")
      (node (ref "CON4") (pin "5") (pinfunction "5_5") (pintype "bidirectional"))
      (node (ref "IC6") (pin "5") (pinfunction "Y_5") (pintype "output"))
      (node (ref "R32") (pin "1") (pinfunction "1_1") (pintype "passive"))
    )
    (net (code "19") (name "DT_1") (class "Default")
      (node (ref "IC1") (pin "3") (pinfunction "DI_3") (pintype "input"))
      (node (ref "MOD_1") (pin "DT@12") (pinfunction "DT_DT@12") (pintype "output"))
    )
    (net (code "20") (name "DT_2") (class "Default")
      (node (ref "IC2") (pin "3") (pinfunction "DI_3") (pintype "input"))
      (node (ref "MOD_2") (pin "DT@12") (pinfunction "DT_DT@12") (pintype "output"))
    )
    (net (code "21") (name "DT_3") (class "Default")
      (node (ref "IC3") (pin "3") (pinfunction "DI_3") (pintype "input"))
      (node (ref "MOD_3") (pin "DT@12") (pinfunction "DT_DT@12") (pintype "output"))
    )
    (net (code "22") (name "DT_4") (class "Default")
      (node (ref "IC4") (pin "3") (pinfunction "DI_3") (pintype "input"))
      (node (ref "MOD_4") (pin "DT@12") (pinfunction "DT_DT@12") (pintype "output"))
    )
    (net (code "23") (name "DT_5") (class "Default")
      (node (ref "IC5") (pin "3") (pinfunction "DI_3") (pintype "input"))
      (node (ref "MOD_5") (pin "DT@12") (pinfunction "DT_DT@12") (pintype "output"))
    )
    (net (code "24") (name "DT_6") (class "Default")
      (node (ref "IC6") (pin "3") (pinfunction "DI_3") (pintype "input"))
      (node (ref "MOD_6") (pin "DT@12") (pinfunction "DT_DT@12") (pintype "output"))
    )
    (net (code "25") (name "FRQSEL0") (class "Default")
      (node (ref "IC9") (pin "24") (pinfunction "FRQSEL0_24") (pintype "bidirectional"))
      (node (ref "R25") (pin "1") (pinfunction "1_1") (pintype "passive"))
      (node (ref "R26") (pin "2") (pinfunction "2_2") (pintype "passive"))
    )
    (net (code "26") (name "GND") (class "Default")
      (node (ref "38.4_MHZ") (pin "PIN_2") (pinfunction "GND_2_PIN_2") (pintype "power_in"))
      (node (ref "38.4_MHZ") (pin "PIN_4") (pinfunction "GND_1_PIN_4") (pintype "power_in"))
      (node (ref "C13") (pin "1") (pinfunction "1_1") (pintype "passive"))
      (node (ref "C14") (pin "1") (pinfunction "1_1") (pintype "passive"))
      (node (ref "C15") (pin "1") (pinfunction "1_1") (pintype "passive"))
      (node (ref "C16") (pin "1") (pinfunction "1_1") (pintype "passive"))
      (node (ref "C18") (pin "2") (pinfunction "2_2") (pintype "passive"))
      (node (ref "C19") (pin "1") (pinfunction "1_1") (pintype "passive"))
      (node (ref "C20") (pin "1") (pinfunction "1_1") (pintype "passive"))
      (node (ref "C21") (pin "2") (pinfunction "2_2") (pintype "passive"))
      (node (ref "C22") (pin "-") (pinfunction "-_-") (pintype "passive"))
      (node (ref "C23") (pin "-") (pinfunction "-_-") (pintype "passive"))
      (node (ref "C24") (pin "2") (pinfunction "2_2") (pintype "passive"))
      (node (ref "C25") (pin "-") (pinfunction "-_-") (pintype "passive"))
      (node (ref "C26") (pin "1") (pinfunction "1_1") (pintype "passive"))
      (node (ref "C27") (pin "1") (pinfunction "1_1") (pintype "passive"))
      (node (ref "C28") (pin "1") (pinfunction "1_1") (pintype "passive"))
      (node (ref "C29") (pin "1") (pinfunction "1_1") (pintype "passive"))
      (node (ref "C30") (pin "1") (pinfunction "1_1") (pintype "passive"))
      (node (ref "C31") (pin "1") (pinfunction "1_1") (pintype "passive"))
      (node (ref "D2") (pin "A") (pinfunction "A_A") (pintype "passive"))
      (node (ref "IC1") (pin "4") (pinfunction "GND_4") (pintype "power_in"))
      (node (ref "IC1") (pin "7") (pinfunction "B_7") (pintype "input"))
      (node (ref "IC1") (pin "8") (pinfunction "A_8") (pintype "input"))
      (node (ref "IC10") (pin "3") (pinfunction "DI_3") (pintype "input"))
      (node (ref "IC10") (pin "4") (pinfunction "GND_4") (pintype "power_in"))
      (node (ref "IC11") (pin "GND") (pinfunction "GND_GND") (pintype "input"))
      (node (ref "IC12") (pin "2") (pinfunction "GND_2") (pintype "power_in"))
      (node (ref "IC12") (pin "4") (pinfunction "GND_4") (pintype "power_in"))
      (node (ref "IC2") (pin "4") (pinfunction "GND_4") (pintype "power_in"))
      (node (ref "IC2") (pin "7") (pinfunction "B_7") (pintype "input"))
      (node (ref "IC2") (pin "8") (pinfunction "A_8") (pintype "input"))
      (node (ref "IC3") (pin "4") (pinfunction "GND_4") (pintype "power_in"))
      (node (ref "IC3") (pin "7") (pinfunction "B_7") (pintype "input"))
      (node (ref "IC3") (pin "8") (pinfunction "A_8") (pintype "input"))
      (node (ref "IC4") (pin "4") (pinfunction "GND_4") (pintype "power_in"))
      (node (ref "IC4") (pin "7") (pinfunction "B_7") (pintype "input"))
      (node (ref "IC4") (pin "8") (pinfunction "A_8") (pintype "input"))
      (node (ref "IC5") (pin "4") (pinfunction "GND_4") (pintype "power_in"))
      (node (ref "IC5") (pin "7") (pinfunction "B_7") (pintype "input"))
      (node (ref "IC5") (pin "8") (pinfunction "A_8") (pintype "input"))
      (node (ref "IC6") (pin "4") (pinfunction "GND_4") (pintype "power_in"))
      (node (ref "IC6") (pin "7") (pinfunction "B_7") (pintype "input"))
      (node (ref "IC6") (pin "8") (pinfunction "A_8") (pintype "input"))
      (node (ref "IC9") (pin "11") (pinfunction "RATE0_11") (pintype "bidirectional"))
      (node (ref "IC9") (pin "15") (pinfunction "RATE1_15") (pintype "bidirectional"))
      (node (ref "IC9") (pin "19") (pinfunction "DEC_19") (pintype "bidirectional"))
      (node (ref "IC9") (pin "2") (pinfunction "FRQTBL_2") (pintype "bidirectional"))
      (node (ref "IC9") (pin "20") (pinfunction "INC_20") (pintype "bidirectional"))
      (node (ref "IC9") (pin "30") (pinfunction "SFOUT1_30") (pintype "bidirectional"))
      (node (ref "IC9") (pin "31") (pinfunction "GND__31") (pintype "bidirectional"))
      (node (ref "IC9") (pin "8") (pinfunction "GND_8") (pintype "bidirectional"))
      (node (ref "L3") (pin "3") (pinfunction "3_3") (pintype "power_in"))
      (node (ref "LLK") (pin "A") (pinfunction "A_A") (pintype "passive"))
      (node (ref "R10") (pin "2") (pinfunction "2_2") (pintype "passive"))
      (node (ref "R13") (pin "1") (pinfunction "1_1") (pintype "passive"))
      (node (ref "R15") (pin "1") (pinfunction "1_1") (pintype "passive"))
      (node (ref "R17") (pin "1") (pinfunction "1_1") (pintype "passive"))
      (node (ref "R20") (pin "1") (pinfunction "1_1") (pintype "passive"))
      (node (ref "R22") (pin "1") (pinfunction "1_1") (pintype "passive"))
      (node (ref "R26") (pin "1") (pinfunction "1_1") (pintype "passive"))
      (node (ref "R9") (pin "2") (pinfunction "2_2") (pintype "passive"))
      (node (ref "SH1") (pin "P$1") (pinfunction "GND_P$1") (pintype "power_in"))
      (node (ref "SH1") (pin "P$10") (pinfunction "GND_P$10") (pintype "power_in"))
      (node (ref "SH1") (pin "P$11") (pinfunction "GND_P$11") (pintype "power_in"))
      (node (ref "SH1") (pin "P$12") (pinfunction "GND_P$12") (pintype "power_in"))
      (node (ref "SH1") (pin "P$2") (pinfunction "GND_P$2") (pintype "power_in"))
      (node (ref "SH1") (pin "P$3") (pinfunction "GND_P$3") (pintype "power_in"))
      (node (ref "SH1") (pin "P$4") (pinfunction "GND_P$4") (pintype "power_in"))
      (node (ref "SH1") (pin "P$5") (pinfunction "GND_P$5") (pintype "power_in"))
      (node (ref "SH1") (pin "P$6") (pinfunction "GND_P$6") (pintype "power_in"))
      (node (ref "SH1") (pin "P$7") (pinfunction "GND_P$7") (pintype "power_in"))
      (node (ref "SH1") (pin "P$8") (pinfunction "GND_P$8") (pintype "power_in"))
      (node (ref "SH1") (pin "P$9") (pinfunction "GND_P$9") (pintype "power_in"))
    )
    (net (code "27") (name "GNDA") (class "Default")
      (node (ref "C1") (pin "2") (pinfunction "2_2") (pintype "passive"))
      (node (ref "C11") (pin "2") (pinfunction "2_2") (pintype "passive"))
      (node (ref "C12") (pin "2") (pinfunction "2_2") (pintype "passive"))
      (node (ref "C7") (pin "2") (pinfunction "-_2") (pintype "passive"))
      (node (ref "IC8") (pin "2") (pinfunction "GND_2") (pintype "power_in"))
      (node (ref "MOD_4") (pin "GND@1") (pinfunction "GND_GND@1") (pintype "power_in"))
      (node (ref "MOD_4") (pin "GND@10") (pinfunction "GND_GND@10") (pintype "power_in"))
      (node (ref "MOD_4") (pin "GND@14") (pinfunction "GND_GND@14") (pintype "power_in"))
      (node (ref "MOD_4") (pin "GND@2") (pinfunction "GND_GND@2") (pintype "power_in"))
      (node (ref "MOD_4") (pin "GND@3") (pinfunction "GND_GND@3") (pintype "power_in"))
      (node (ref "MOD_4") (pin "GND@4") (pinfunction "GND_GND@4") (pintype "power_in"))
      (node (ref "MOD_4") (pin "GND@5") (pinfunction "GND_GND@5") (pintype "power_in"))
      (node (ref "MOD_4") (pin "GND@6") (pinfunction "GND_GND@6") (pintype "power_in"))
      (node (ref "MOD_4") (pin "GND@7") (pinfunction "GND_GND@7") (pintype "power_in"))
      (node (ref "MOD_4") (pin "GND@8") (pinfunction "GND_GND@8") (pintype "power_in"))
      (node (ref "MOD_4") (pin "GND@9") (pinfunction "GND_GND@9") (pintype "power_in"))
      (node (ref "MOD_4") (pin "V1") (pinfunction "GND_V1") (pintype "power_in"))
      (node (ref "MOD_4") (pin "V10") (pinfunction "GND_V10") (pintype "power_in"))
      (node (ref "MOD_4") (pin "V11") (pinfunction "GND_V11") (pintype "power_in"))
      (node (ref "MOD_4") (pin "V12") (pinfunction "GND_V12") (pintype "power_in"))
      (node (ref "MOD_4") (pin "V13") (pinfunction "GND_V13") (pintype "power_in"))
      (node (ref "MOD_4") (pin "V14") (pinfunction "GND_V14") (pintype "power_in"))
      (node (ref "MOD_4") (pin "V15") (pinfunction "GND_V15") (pintype "power_in"))
      (node (ref "MOD_4") (pin "V16") (pinfunction "GND_V16") (pintype "power_in"))
      (node (ref "MOD_4") (pin "V17") (pinfunction "GND_V17") (pintype "power_in"))
      (node (ref "MOD_4") (pin "V18") (pinfunction "GND_V18") (pintype "power_in"))
      (node (ref "MOD_4") (pin "V19") (pinfunction "GND_V19") (pintype "power_in"))
      (node (ref "MOD_4") (pin "V2") (pinfunction "GND_V2") (pintype "power_in"))
      (node (ref "MOD_4") (pin "V20") (pinfunction "GND_V20") (pintype "power_in"))
      (node (ref "MOD_4") (pin "V21") (pinfunction "GND_V21") (pintype "power_in"))
      (node (ref "MOD_4") (pin "V22") (pinfunction "GND_V22") (pintype "power_in"))
      (node (ref "MOD_4") (pin "V23") (pinfunction "GND_V23") (pintype "power_in"))
      (node (ref "MOD_4") (pin "V24") (pinfunction "GND_V24") (pintype "power_in"))
      (node (ref "MOD_4") (pin "V25") (pinfunction "GND_V25") (pintype "power_in"))
      (node (ref "MOD_4") (pin "V26") (pinfunction "GND_V26") (pintype "power_in"))
      (node (ref "MOD_4") (pin "V27") (pinfunction "GND_V27") (pintype "power_in"))
      (node (ref "MOD_4") (pin "V28") (pinfunction "GND_V28") (pintype "power_in"))
      (node (ref "MOD_4") (pin "V29") (pinfunction "GND_V29") (pintype "power_in"))
      (node (ref "MOD_4") (pin "V3") (pinfunction "GND_V3") (pintype "power_in"))
      (node (ref "MOD_4") (pin "V30") (pinfunction "GND_V30") (pintype "power_in"))
      (node (ref "MOD_4") (pin "V4") (pinfunction "GND_V4") (pintype "power_in"))
      (node (ref "MOD_4") (pin "V5") (pinfunction "GND_V5") (pintype "power_in"))
      (node (ref "MOD_4") (pin "V6") (pinfunction "GND_V6") (pintype "power_in"))
      (node (ref "MOD_4") (pin "V7") (pinfunction "GND_V7") (pintype "power_in"))
      (node (ref "MOD_4") (pin "V8") (pinfunction "GND_V8") (pintype "power_in"))
      (node (ref "MOD_4") (pin "V9") (pinfunction "GND_V9") (pintype "power_in"))
      (node (ref "MOD_5") (pin "GND@1") (pinfunction "GND_GND@1") (pintype "power_in"))
      (node (ref "MOD_5") (pin "GND@10") (pinfunction "GND_GND@10") (pintype "power_in"))
      (node (ref "MOD_5") (pin "GND@14") (pinfunction "GND_GND@14") (pintype "power_in"))
      (node (ref "MOD_5") (pin "GND@2") (pinfunction "GND_GND@2") (pintype "power_in"))
      (node (ref "MOD_5") (pin "GND@3") (pinfunction "GND_GND@3") (pintype "power_in"))
      (node (ref "MOD_5") (pin "GND@4") (pinfunction "GND_GND@4") (pintype "power_in"))
      (node (ref "MOD_5") (pin "GND@5") (pinfunction "GND_GND@5") (pintype "power_in"))
      (node (ref "MOD_5") (pin "GND@6") (pinfunction "GND_GND@6") (pintype "power_in"))
      (node (ref "MOD_5") (pin "GND@7") (pinfunction "GND_GND@7") (pintype "power_in"))
      (node (ref "MOD_5") (pin "GND@8") (pinfunction "GND_GND@8") (pintype "power_in"))
      (node (ref "MOD_5") (pin "GND@9") (pinfunction "GND_GND@9") (pintype "power_in"))
      (node (ref "MOD_5") (pin "V1") (pinfunction "GND_V1") (pintype "power_in"))
      (node (ref "MOD_5") (pin "V10") (pinfunction "GND_V10") (pintype "power_in"))
      (node (ref "MOD_5") (pin "V11") (pinfunction "GND_V11") (pintype "power_in"))
      (node (ref "MOD_5") (pin "V12") (pinfunction "GND_V12") (pintype "power_in"))
      (node (ref "MOD_5") (pin "V13") (pinfunction "GND_V13") (pintype "power_in"))
      (node (ref "MOD_5") (pin "V14") (pinfunction "GND_V14") (pintype "power_in"))
      (node (ref "MOD_5") (pin "V15") (pinfunction "GND_V15") (pintype "power_in"))
      (node (ref "MOD_5") (pin "V16") (pinfunction "GND_V16") (pintype "power_in"))
      (node (ref "MOD_5") (pin "V17") (pinfunction "GND_V17") (pintype "power_in"))
      (node (ref "MOD_5") (pin "V18") (pinfunction "GND_V18") (pintype "power_in"))
      (node (ref "MOD_5") (pin "V19") (pinfunction "GND_V19") (pintype "power_in"))
      (node (ref "MOD_5") (pin "V2") (pinfunction "GND_V2") (pintype "power_in"))
      (node (ref "MOD_5") (pin "V20") (pinfunction "GND_V20") (pintype "power_in"))
      (node (ref "MOD_5") (pin "V21") (pinfunction "GND_V21") (pintype "power_in"))
      (node (ref "MOD_5") (pin "V22") (pinfunction "GND_V22") (pintype "power_in"))
      (node (ref "MOD_5") (pin "V23") (pinfunction "GND_V23") (pintype "power_in"))
      (node (ref "MOD_5") (pin "V24") (pinfunction "GND_V24") (pintype "power_in"))
      (node (ref "MOD_5") (pin "V25") (pinfunction "GND_V25") (pintype "power_in"))
      (node (ref "MOD_5") (pin "V26") (pinfunction "GND_V26") (pintype "power_in"))
      (node (ref "MOD_5") (pin "V27") (pinfunction "GND_V27") (pintype "power_in"))
      (node (ref "MOD_5") (pin "V28") (pinfunction "GND_V28") (pintype "power_in"))
      (node (ref "MOD_5") (pin "V29") (pinfunction "GND_V29") (pintype "power_in"))
      (node (ref "MOD_5") (pin "V3") (pinfunction "GND_V3") (pintype "power_in"))
      (node (ref "MOD_5") (pin "V30") (pinfunction "GND_V30") (pintype "power_in"))
      (node (ref "MOD_5") (pin "V4") (pinfunction "GND_V4") (pintype "power_in"))
      (node (ref "MOD_5") (pin "V5") (pinfunction "GND_V5") (pintype "power_in"))
      (node (ref "MOD_5") (pin "V6") (pinfunction "GND_V6") (pintype "power_in"))
      (node (ref "MOD_5") (pin "V7") (pinfunction "GND_V7") (pintype "power_in"))
      (node (ref "MOD_5") (pin "V8") (pinfunction "GND_V8") (pintype "power_in"))
      (node (ref "MOD_5") (pin "V9") (pinfunction "GND_V9") (pintype "power_in"))
      (node (ref "MOD_6") (pin "GND@1") (pinfunction "GND_GND@1") (pintype "power_in"))
      (node (ref "MOD_6") (pin "GND@10") (pinfunction "GND_GND@10") (pintype "power_in"))
      (node (ref "MOD_6") (pin "GND@14") (pinfunction "GND_GND@14") (pintype "power_in"))
      (node (ref "MOD_6") (pin "GND@2") (pinfunction "GND_GND@2") (pintype "power_in"))
      (node (ref "MOD_6") (pin "GND@3") (pinfunction "GND_GND@3") (pintype "power_in"))
      (node (ref "MOD_6") (pin "GND@4") (pinfunction "GND_GND@4") (pintype "power_in"))
      (node (ref "MOD_6") (pin "GND@5") (pinfunction "GND_GND@5") (pintype "power_in"))
      (node (ref "MOD_6") (pin "GND@6") (pinfunction "GND_GND@6") (pintype "power_in"))
      (node (ref "MOD_6") (pin "GND@7") (pinfunction "GND_GND@7") (pintype "power_in"))
      (node (ref "MOD_6") (pin "GND@8") (pinfunction "GND_GND@8") (pintype "power_in"))
      (node (ref "MOD_6") (pin "GND@9") (pinfunction "GND_GND@9") (pintype "power_in"))
      (node (ref "MOD_6") (pin "V1") (pinfunction "GND_V1") (pintype "power_in"))
      (node (ref "MOD_6") (pin "V10") (pinfunction "GND_V10") (pintype "power_in"))
      (node (ref "MOD_6") (pin "V11") (pinfunction "GND_V11") (pintype "power_in"))
      (node (ref "MOD_6") (pin "V12") (pinfunction "GND_V12") (pintype "power_in"))
      (node (ref "MOD_6") (pin "V13") (pinfunction "GND_V13") (pintype "power_in"))
      (node (ref "MOD_6") (pin "V14") (pinfunction "GND_V14") (pintype "power_in"))
      (node (ref "MOD_6") (pin "V15") (pinfunction "GND_V15") (pintype "power_in"))
      (node (ref "MOD_6") (pin "V16") (pinfunction "GND_V16") (pintype "power_in"))
      (node (ref "MOD_6") (pin "V17") (pinfunction "GND_V17") (pintype "power_in"))
      (node (ref "MOD_6") (pin "V18") (pinfunction "GND_V18") (pintype "power_in"))
      (node (ref "MOD_6") (pin "V19") (pinfunction "GND_V19") (pintype "power_in"))
      (node (ref "MOD_6") (pin "V2") (pinfunction "GND_V2") (pintype "power_in"))
      (node (ref "MOD_6") (pin "V20") (pinfunction "GND_V20") (pintype "power_in"))
      (node (ref "MOD_6") (pin "V21") (pinfunction "GND_V21") (pintype "power_in"))
      (node (ref "MOD_6") (pin "V22") (pinfunction "GND_V22") (pintype "power_in"))
      (node (ref "MOD_6") (pin "V23") (pinfunction "GND_V23") (pintype "power_in"))
      (node (ref "MOD_6") (pin "V24") (pinfunction "GND_V24") (pintype "power_in"))
      (node (ref "MOD_6") (pin "V25") (pinfunction "GND_V25") (pintype "power_in"))
      (node (ref "MOD_6") (pin "V26") (pinfunction "GND_V26") (pintype "power_in"))
      (node (ref "MOD_6") (pin "V27") (pinfunction "GND_V27") (pintype "power_in"))
      (node (ref "MOD_6") (pin "V28") (pinfunction "GND_V28") (pintype "power_in"))
      (node (ref "MOD_6") (pin "V29") (pinfunction "GND_V29") (pintype "power_in"))
      (node (ref "MOD_6") (pin "V3") (pinfunction "GND_V3") (pintype "power_in"))
      (node (ref "MOD_6") (pin "V30") (pinfunction "GND_V30") (pintype "power_in"))
      (node (ref "MOD_6") (pin "V4") (pinfunction "GND_V4") (pintype "power_in"))
      (node (ref "MOD_6") (pin "V5") (pinfunction "GND_V5") (pintype "power_in"))
      (node (ref "MOD_6") (pin "V6") (pinfunction "GND_V6") (pintype "power_in"))
      (node (ref "MOD_6") (pin "V7") (pinfunction "GND_V7") (pintype "power_in"))
      (node (ref "MOD_6") (pin "V8") (pinfunction "GND_V8") (pintype "power_in"))
      (node (ref "MOD_6") (pin "V9") (pinfunction "GND_V9") (pintype "power_in"))
      (node (ref "R10") (pin "1") (pinfunction "1_1") (pintype "passive"))
    )
    (net (code "28") (name "GND_CABLE") (class "Default")
      (node (ref "CON4") (pin "2") (pinfunction "2_2") (pintype "bidirectional"))
      (node (ref "L3") (pin "2") (pinfunction "2_2") (pintype "power_in"))
    )
    (net (code "29") (name "LOL") (class "Default")
      (node (ref "IC9") (pin "18") (pinfunction "LOL_18") (pintype "bidirectional"))
      (node (ref "R18") (pin "2") (pinfunction "2_2") (pintype "passive"))
    )
    (net (code "30") (name "Net-(38.4_MHZ-CON_1)") (class "Default")
      (node (ref "38.4_MHZ") (pin "PIN_1") (pinfunction "CON_1_PIN_1") (pintype "bidirectional"))
      (node (ref "IC9") (pin "6") (pinfunction "XA_6") (pintype "bidirectional"))
    )
    (net (code "31") (name "Net-(38.4_MHZ-CON_2)") (class "Default")
      (node (ref "38.4_MHZ") (pin "PIN_3") (pinfunction "CON_2_PIN_3") (pintype "bidirectional"))
      (node (ref "IC9") (pin "7") (pinfunction "XB_7") (pintype "bidirectional"))
    )
    (net (code "32") (name "Net-(C21-Pad1)") (class "Default")
      (node (ref "C21") (pin "1") (pinfunction "1_1") (pintype "passive"))
      (node (ref "C22") (pin "+") (pinfunction "+_+") (pintype "passive"))
      (node (ref "D2") (pin "C") (pinfunction "C_C") (pintype "passive"))
      (node (ref "IC11") (pin "IN") (pinfunction "IN_IN") (pintype "input"))
      (node (ref "L3") (pin "4") (pinfunction "4_4") (pintype "power_in"))
    )
    (net (code "33") (name "Net-(IC7-BYP)") (class "Default")
      (node (ref "C9") (pin "1") (pinfunction "1_1") (pintype "passive"))
      (node (ref "IC7") (pin "4") (pinfunction "BYP_4") (pintype "bidirectional"))
    )
    (net (code "34") (name "Net-(IC8-BYP)") (class "Default")
      (node (ref "C11") (pin "1") (pinfunction "1_1") (pintype "passive"))
      (node (ref "IC8") (pin "4") (pinfunction "BYP_4") (pintype "bidirectional"))
    )
    (net (code "35") (name "Net-(IC9A-CKIN+)") (class "Default")
      (node (ref "C17") (pin "1") (pinfunction "1_1") (pintype "passive"))
      (node (ref "IC9") (pin "16") (pinfunction "CKIN+_16") (pintype "bidirectional"))
    )
    (net (code "36") (name "Net-(IC9A-CKIN-)") (class "Default")
      (node (ref "C18") (pin "1") (pinfunction "1_1") (pintype "passive"))
      (node (ref "IC9") (pin "17") (pinfunction "CKIN-_17") (pintype "bidirectional"))
    )
    (net (code "37") (name "Net-(LLK-PadC)") (class "Default")
      (node (ref "LLK") (pin "C") (pinfunction "C_C") (pintype "passive"))
      (node (ref "R18") (pin "1") (pinfunction "1_1") (pintype "passive"))
    )
    (net (code "38") (name "Net-(PWR-PadA)") (class "Default")
      (node (ref "PWR") (pin "A") (pinfunction "A_A") (pintype "passive"))
      (node (ref "R17") (pin "2") (pinfunction "2_2") (pintype "passive"))
    )
    (net (code "39") (name "RO_CLK") (class "Default")
      (node (ref "C17") (pin "2") (pinfunction "2_2") (pintype "passive"))
      (node (ref "IC10") (pin "2") (pinfunction "RO_2") (pintype "output"))
      (node (ref "R19") (pin "1") (pinfunction "1_1") (pintype "passive"))
      (node (ref "R20") (pin "2") (pinfunction "2_2") (pintype "passive"))
    )
    (net (code "40") (name "VDD") (class "Default")
      (node (ref "C14") (pin "2") (pinfunction "2_2") (pintype "passive"))
      (node (ref "C15") (pin "2") (pinfunction "2_2") (pintype "passive"))
      (node (ref "C16") (pin "2") (pinfunction "2_2") (pintype "passive"))
      (node (ref "C20") (pin "2") (pinfunction "2_2") (pintype "passive"))
      (node (ref "IC9") (pin "10") (pinfunction "VDD_2_10") (pintype "bidirectional"))
      (node (ref "IC9") (pin "25") (pinfunction "FRQSEL1_25") (pintype "bidirectional"))
      (node (ref "IC9") (pin "26") (pinfunction "FRQSEL2_26") (pintype "bidirectional"))
      (node (ref "IC9") (pin "27") (pinfunction "FRQSEL3_27") (pintype "bidirectional"))
      (node (ref "IC9") (pin "32") (pinfunction "VDD_3_32") (pintype "bidirectional"))
      (node (ref "IC9") (pin "33") (pinfunction "SFOUT0_33") (pintype "bidirectional"))
      (node (ref "IC9") (pin "5") (pinfunction "VDD_1_5") (pintype "bidirectional"))
      (node (ref "L2") (pin "2") (pinfunction "2_2") (pintype "passive"))
      (node (ref "R16") (pin "2") (pinfunction "2_2") (pintype "passive"))
      (node (ref "R21") (pin "2") (pinfunction "2_2") (pintype "passive"))
    )
    (net (code "41") (name "VDD_2") (class "Default")
      (node (ref "L1") (pin "2") (pinfunction "2_2") (pintype "passive"))
      (node (ref "R12") (pin "2") (pinfunction "2_2") (pintype "passive"))
      (node (ref "R14") (pin "2") (pinfunction "2_2") (pintype "passive"))
      (node (ref "R19") (pin "2") (pinfunction "2_2") (pintype "passive"))
      (node (ref "R25") (pin "2") (pinfunction "2_2") (pintype "passive"))
    )
    (net (code "42") (name "unconnected-(IC1-RO-Pad2)") (class "Default")
      (node (ref "IC1") (pin "2") (pinfunction "RO_2") (pintype "output"))
    )
    (net (code "43") (name "unconnected-(IC2-RO-Pad2)") (class "Default")
      (node (ref "IC2") (pin "2") (pinfunction "RO_2") (pintype "output"))
    )
    (net (code "44") (name "unconnected-(IC3-RO-Pad2)") (class "Default")
      (node (ref "IC3") (pin "2") (pinfunction "RO_2") (pintype "output"))
    )
    (net (code "45") (name "unconnected-(IC4-RO-Pad2)") (class "Default")
      (node (ref "IC4") (pin "2") (pinfunction "RO_2") (pintype "output"))
    )
    (net (code "46") (name "unconnected-(IC5-RO-Pad2)") (class "Default")
      (node (ref "IC5") (pin "2") (pinfunction "RO_2") (pintype "output"))
    )
    (net (code "47") (name "unconnected-(IC6-RO-Pad2)") (class "Default")
      (node (ref "IC6") (pin "2") (pinfunction "RO_2") (pintype "output"))
    )
    (net (code "48") (name "unconnected-(IC9A-CKOUT2+-Pad35)") (class "Default")
      (node (ref "IC9") (pin "35") (pinfunction "CKOUT2+_35") (pintype "bidirectional"))
    )
    (net (code "49") (name "unconnected-(IC9A-CKOUT2--Pad34)") (class "Default")
      (node (ref "IC9") (pin "34") (pinfunction "CKOUT2-_34") (pintype "bidirectional"))
    )
    (net (code "50") (name "unconnected-(IC9A-LOS-Pad3)") (class "Default")
      (node (ref "IC9") (pin "3") (pinfunction "LOS_3") (pintype "bidirectional"))
    )
    (net (code "51") (name "unconnected-(IC9A-NC_1-Pad4)") (class "Default")
      (node (ref "IC9") (pin "4") (pinfunction "NC_1_4") (pintype "bidirectional"))
    )
    (net (code "52") (name "unconnected-(IC9A-NC_2-Pad9)") (class "Default")
      (node (ref "IC9") (pin "9") (pinfunction "NC_2_9") (pintype "bidirectional"))
    )
    (net (code "53") (name "unconnected-(IC9A-NC_3-Pad12)") (class "Default")
      (node (ref "IC9") (pin "12") (pinfunction "NC_3_12") (pintype "bidirectional"))
    )
    (net (code "54") (name "unconnected-(IC9A-NC_4-Pad13)") (class "Default")
      (node (ref "IC9") (pin "13") (pinfunction "NC_4_13") (pintype "bidirectional"))
    )
    (net (code "55") (name "unconnected-(IC9A-NC_5-Pad21)") (class "Default")
      (node (ref "IC9") (pin "21") (pinfunction "NC_5_21") (pintype "bidirectional"))
    )
    (net (code "56") (name "unconnected-(IC9A-NC_6-Pad36)") (class "Default")
      (node (ref "IC9") (pin "36") (pinfunction "NC_6_36") (pintype "bidirectional"))
    )
    (net (code "57") (name "unconnected-(IC10-Y-Pad5)") (class "Default")
      (node (ref "IC10") (pin "5") (pinfunction "Y_5") (pintype "output"))
    )
    (net (code "58") (name "unconnected-(IC10-Z-Pad6)") (class "Default")
      (node (ref "IC10") (pin "6") (pinfunction "Z_6") (pintype "output"))
    )
    (net (code "59") (name "~{DT1}") (class "Default")
      (node (ref "CON3") (pin "6") (pinfunction "6_6") (pintype "bidirectional"))
      (node (ref "IC1") (pin "6") (pinfunction "Z_6") (pintype "output"))
      (node (ref "R27") (pin "2") (pinfunction "2_2") (pintype "passive"))
    )
    (net (code "60") (name "~{DT2}") (class "Default")
      (node (ref "CON3") (pin "5") (pinfunction "5_5") (pintype "bidirectional"))
      (node (ref "IC2") (pin "6") (pinfunction "Z_6") (pintype "output"))
      (node (ref "R28") (pin "2") (pinfunction "2_2") (pintype "passive"))
    )
    (net (code "61") (name "~{DT3}") (class "Default")
      (node (ref "CON3") (pin "2") (pinfunction "2_2") (pintype "bidirectional"))
      (node (ref "IC3") (pin "6") (pinfunction "Z_6") (pintype "output"))
      (node (ref "R29") (pin "2") (pinfunction "2_2") (pintype "passive"))
    )
    (net (code "62") (name "~{DT4}") (class "Default")
      (node (ref "CON4") (pin "8") (pinfunction "8_8") (pintype "bidirectional"))
      (node (ref "IC4") (pin "6") (pinfunction "Z_6") (pintype "output"))
      (node (ref "R30") (pin "2") (pinfunction "2_2") (pintype "passive"))
    )
    (net (code "63") (name "~{DT5}") (class "Default")
      (node (ref "CON4") (pin "3") (pinfunction "3_3") (pintype "bidirectional"))
      (node (ref "IC5") (pin "6") (pinfunction "Z_6") (pintype "output"))
      (node (ref "R31") (pin "2") (pinfunction "2_2") (pintype "passive"))
    )
    (net (code "64") (name "~{DT6}") (class "Default")
      (node (ref "CON4") (pin "4") (pinfunction "4_4") (pintype "bidirectional"))
      (node (ref "IC6") (pin "6") (pinfunction "Z_6") (pintype "output"))
      (node (ref "R32") (pin "2") (pinfunction "2_2") (pintype "passive"))
    )
    (net (code "65") (name "~{RST}") (class "Default")
      (node (ref "C13") (pin "2") (pinfunction "2_2") (pintype "passive"))
      (node (ref "IC9") (pin "1") (pinfunction "~{RST}_1") (pintype "bidirectional"))
      (node (ref "R16") (pin "1") (pinfunction "1_1") (pintype "passive"))
    )
  )
)
